# Schema1.net
KiCad netlist of a schematic drawn in Altium Designer
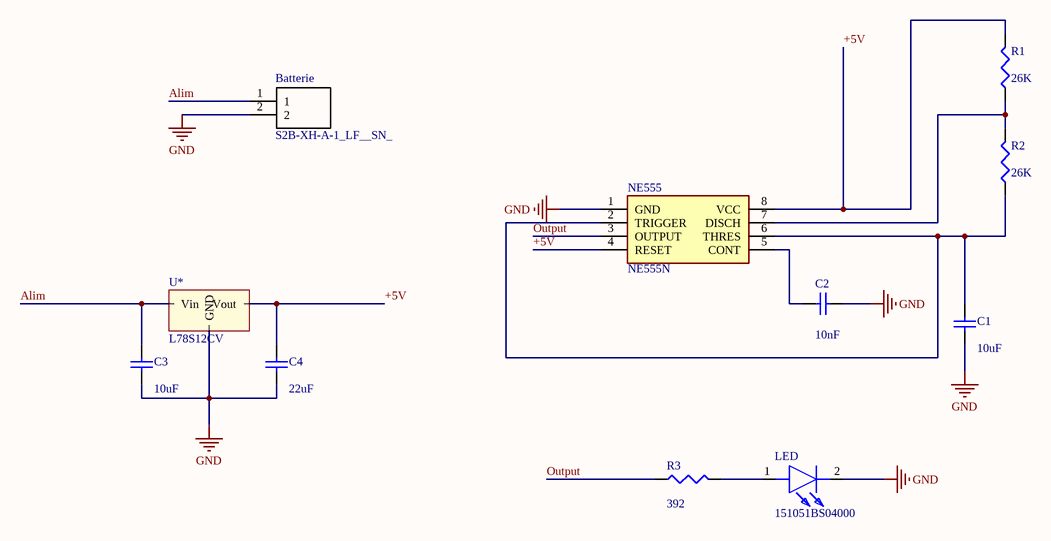
[diagram p0: Schema1.SchDoc]

(export (version "E")
  (design (tool "Eeschema 10.0.6"))
  (components
    (comp (ref "Batterie")
      (value "S2B-XH-A-1_LF__SN_")
      (footprint "SamacSys:S2B-XH-A")
      (description "Connector")
      (fields (field (name "MANUFACTURER_PART_NUMBER") "S2B-XH-A-1(LF)(SN)"))
      (libsource (lib "SamacSys") (part "S2B-XH-A-1_LF__SN_"))
    )
    (comp (ref "C1")
      (value "10uF")
      (footprint "C1206")
      (description "Capacitor (Semiconductor SIM Model)")
      (fields (field (name "PUBLISHER") "Altium Limited"))
      (libsource (lib "Miscellaneous Devices") (part "Cap Semi"))
    )
    (comp (ref "C2")
      (value "10nF")
      (footprint "C1206")
      (description "Capacitor (Semiconductor SIM Model)")
      (fields (field (name "PUBLISHER") "Altium Limited"))
      (libsource (lib "Miscellaneous Devices") (part "Cap Semi"))
    )
    (comp (ref "C3")
      (value "10uF")
      (footprint "C1206")
      (description "Capacitor (Semiconductor SIM Model)")
      (fields (field (name "PUBLISHER") "Altium Limited"))
      (libsource (lib "Miscellaneous Devices") (part "Cap Semi"))
    )
    (comp (ref "C4")
      (value "22uF")
      (footprint "C1206")
      (description "Capacitor (Semiconductor SIM Model)")
      (fields (field (name "PUBLISHER") "Altium Limited"))
      (libsource (lib "Miscellaneous Devices") (part "Cap Semi"))
    )
    (comp (ref "LED")
      (value "151051BS04000")
      (footprint "SamacSys:151051BS04000")
      (description "LED")
      (fields (field (name "MOUSER PART NUMBER") "710-151051BS04000"))
      (libsource (lib "*") (part "151051BS04000"))
    )
    (comp (ref "NE555")
      (value "NE555N")
      (footprint "SamacSys:DIP762W56P254L959H533Q8N")
      (description "Integrated Circuit")
      (libsource (lib "*") (part "NE555N"))
    )
    (comp (ref "R1")
      (value "26K")
      (footprint "Resistor 1206")
      (description "Resistor")
      (fields (field (name "PUBLISHER") "Altium Limited"))
      (libsource (lib "Miscellaneous Devices") (part "Res3"))
    )
    (comp (ref "R2")
      (value "26K")
      (footprint "Resistor 1206")
      (description "Resistor")
      (fields (field (name "PUBLISHER") "Altium Limited"))
      (libsource (lib "Miscellaneous Devices") (part "Res3"))
    )
    (comp (ref "R3")
      (value "392")
      (footprint "Resistor 1206")
      (description "Resistor")
      (fields (field (name "PUBLISHER") "Altium Limited"))
      (libsource (lib "Miscellaneous Devices") (part "Res3"))
    )
    (comp (ref "U*")
      (value "L78S12CV")
      (footprint "R-78B")
      (libsource (lib "Robot_2020") (part "Régulateur de tension linéaire"))
    )
  )
  (nets
    (net (code "1") (name "/+5V") (class "Default")
      (node (ref "C4") (pin "2") (pinfunction "2_2") (pintype "passive"))
      (node (ref "NE555") (pin "4") (pinfunction "RESET_4") (pintype "passive"))
      (node (ref "NE555") (pin "8") (pinfunction "VCC_8") (pintype "passive"))
      (node (ref "R1") (pin "2") (pinfunction "2_2") (pintype "passive"))
      (node (ref "U*") (pin "1") (pinfunction "Vout_1") (pintype "passive"))
    )
    (net (code "2") (name "/Alim") (class "Default")
      (node (ref "Batterie") (pin "1") (pinfunction "1_1") (pintype "passive"))
      (node (ref "C3") (pin "1") (pinfunction "1_1") (pintype "passive"))
      (node (ref "U*") (pin "3") (pinfunction "Vin_3") (pintype "passive"))
    )
    (net (code "3") (name "/Output") (class "Default")
      (node (ref "NE555") (pin "3") (pinfunction "OUTPUT_3") (pintype "passive"))
      (node (ref "R3") (pin "1") (pinfunction "1_1") (pintype "passive"))
    )
    (net (code "4") (name "GND") (class "Default")
      (node (ref "Batterie") (pin "2") (pinfunction "2_2") (pintype "passive"))
      (node (ref "C1") (pin "1") (pinfunction "1_1") (pintype "passive"))
      (node (ref "C2") (pin "1") (pinfunction "1_1") (pintype "passive"))
      (node (ref "C3") (pin "2") (pinfunction "2_2") (pintype "passive"))
      (node (ref "C4") (pin "1") (pinfunction "1_1") (pintype "passive"))
      (node (ref "LED") (pin "2") (pinfunction "K_2") (pintype "passive"))
      (node (ref "NE555") (pin "1") (pinfunction "GND_1") (pintype "passive"))
      (node (ref "U*") (pin "2") (pinfunction "GND_2") (pintype "passive"))
    )
    (net (code "5") (name "Net-(LED-A)") (class "Default")
      (node (ref "LED") (pin "1") (pinfunction "A_1") (pintype "passive"))
      (node (ref "R3") (pin "2") (pinfunction "2_2") (pintype "passive"))
    )
    (net (code "6") (name "Net-(NE555-CONT)") (class "Default")
      (node (ref "C2") (pin "2") (pinfunction "2_2") (pintype "passive"))
      (node (ref "NE555") (pin "5") (pinfunction "CONT_5") (pintype "passive"))
    )
    (net (code "7") (name "Net-(NE555-DISCH)") (class "Default")
      (node (ref "NE555") (pin "7") (pinfunction "DISCH_7") (pintype "passive"))
      (node (ref "R1") (pin "1") (pinfunction "1_1") (pintype "passive"))
      (node (ref "R2") (pin "2") (pinfunction "2_2") (pintype "passive"))
    )
    (net (code "8") (name "Net-(NE555-THRES)") (class "Default")
      (node (ref "C1") (pin "2") (pinfunction "2_2") (pintype "passive"))
      (node (ref "NE555") (pin "2") (pinfunction "TRIGGER_2") (pintype "passive"))
      (node (ref "NE555") (pin "6") (pinfunction "THRES_6") (pintype "passive"))
      (node (ref "R2") (pin "1") (pinfunction "1_1") (pintype "passive"))
    )
  )
)
